# Sheet1.net
KiCad netlist of a schematic drawn in Altium Designer
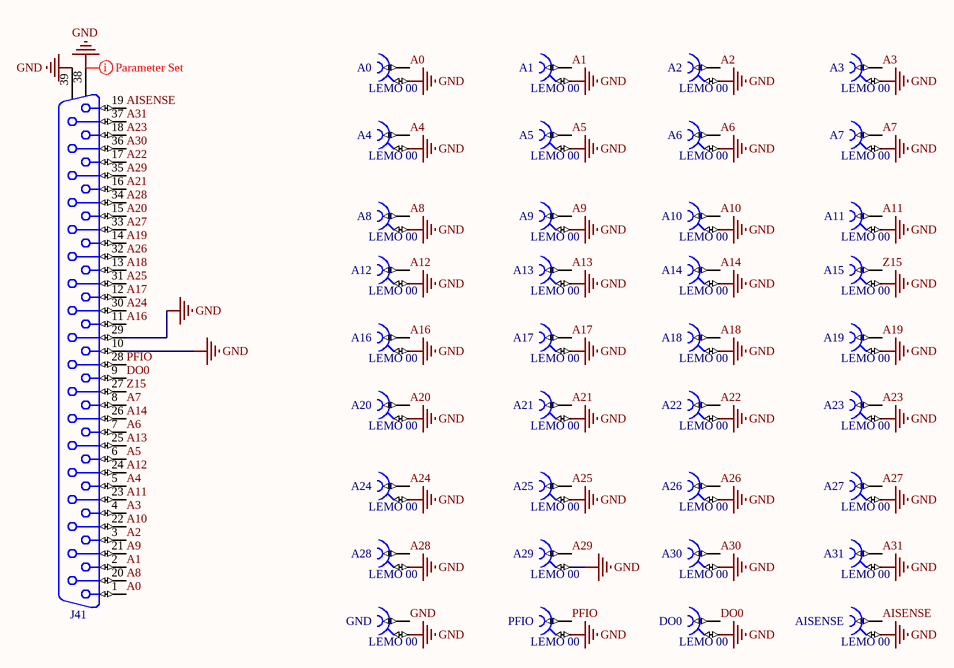
[diagram p0: Sheet1.SchDoc]

(export (version "E")
  (design (tool "Eeschema 10.0.6"))
  (components
    (comp (ref "A0")
      (value "LEMO 00")
      (footprint "LEMO_EPA.00.250.NTN")
      (fields
        (field (name "PART NUMBER") "LEMO_EPA.00.250.NTN")
        (field (name "MANUFACTURER") "LEMO")
        (field (name "MANUFACTURER PART NUMBER") "EPA.00.250.NTN")
        (field (name "AUTHOR") "CERN DEM JLC")
      )
      (libsource (lib "Connectors") (part "Coax_1Female_1Shield"))
    )
    (comp (ref "A1")
      (value "LEMO 00")
      (footprint "LEMO_EPA.00.250.NTN")
      (fields
        (field (name "PART NUMBER") "LEMO_EPA.00.250.NTN")
        (field (name "MANUFACTURER") "LEMO")
        (field (name "MANUFACTURER PART NUMBER") "EPA.00.250.NTN")
        (field (name "AUTHOR") "CERN DEM JLC")
      )
      (libsource (lib "Connectors") (part "Coax_1Female_1Shield"))
    )
    (comp (ref "A2")
      (value "LEMO 00")
      (footprint "LEMO_EPA.00.250.NTN")
      (fields
        (field (name "PART NUMBER") "LEMO_EPA.00.250.NTN")
        (field (name "MANUFACTURER") "LEMO")
        (field (name "MANUFACTURER PART NUMBER") "EPA.00.250.NTN")
        (field (name "AUTHOR") "CERN DEM JLC")
      )
      (libsource (lib "Connectors") (part "Coax_1Female_1Shield"))
    )
    (comp (ref "A3")
      (value "LEMO 00")
      (footprint "LEMO_EPA.00.250.NTN")
      (fields
        (field (name "PART NUMBER") "LEMO_EPA.00.250.NTN")
        (field (name "MANUFACTURER") "LEMO")
        (field (name "MANUFACTURER PART NUMBER") "EPA.00.250.NTN")
        (field (name "AUTHOR") "CERN DEM JLC")
      )
      (libsource (lib "Connectors") (part "Coax_1Female_1Shield"))
    )
    (comp (ref "A4")
      (value "LEMO 00")
      (footprint "LEMO_EPA.00.250.NTN")
      (fields
        (field (name "PART NUMBER") "LEMO_EPA.00.250.NTN")
        (field (name "MANUFACTURER") "LEMO")
        (field (name "MANUFACTURER PART NUMBER") "EPA.00.250.NTN")
        (field (name "AUTHOR") "CERN DEM JLC")
      )
      (libsource (lib "Connectors") (part "Coax_1Female_1Shield"))
    )
    (comp (ref "A5")
      (value "LEMO 00")
      (footprint "LEMO_EPA.00.250.NTN")
      (fields
        (field (name "PART NUMBER") "LEMO_EPA.00.250.NTN")
        (field (name "MANUFACTURER") "LEMO")
        (field (name "MANUFACTURER PART NUMBER") "EPA.00.250.NTN")
        (field (name "AUTHOR") "CERN DEM JLC")
      )
      (libsource (lib "Connectors") (part "Coax_1Female_1Shield"))
    )
    (comp (ref "A6")
      (value "LEMO 00")
      (footprint "LEMO_EPA.00.250.NTN")
      (fields
        (field (name "PART NUMBER") "LEMO_EPA.00.250.NTN")
        (field (name "MANUFACTURER") "LEMO")
        (field (name "MANUFACTURER PART NUMBER") "EPA.00.250.NTN")
        (field (name "AUTHOR") "CERN DEM JLC")
      )
      (libsource (lib "Connectors") (part "Coax_1Female_1Shield"))
    )
    (comp (ref "A7")
      (value "LEMO 00")
      (footprint "LEMO_EPA.00.250.NTN")
      (fields
        (field (name "PART NUMBER") "LEMO_EPA.00.250.NTN")
        (field (name "MANUFACTURER") "LEMO")
        (field (name "MANUFACTURER PART NUMBER") "EPA.00.250.NTN")
        (field (name "AUTHOR") "CERN DEM JLC")
      )
      (libsource (lib "Connectors") (part "Coax_1Female_1Shield"))
    )
    (comp (ref "A8")
      (value "LEMO 00")
      (footprint "LEMO_EPA.00.250.NTN")
      (fields
        (field (name "PART NUMBER") "LEMO_EPA.00.250.NTN")
        (field (name "MANUFACTURER") "LEMO")
        (field (name "MANUFACTURER PART NUMBER") "EPA.00.250.NTN")
        (field (name "AUTHOR") "CERN DEM JLC")
      )
      (libsource (lib "Connectors") (part "Coax_1Female_1Shield"))
    )
    (comp (ref "A9")
      (value "LEMO 00")
      (footprint "LEMO_EPA.00.250.NTN")
      (fields
        (field (name "PART NUMBER") "LEMO_EPA.00.250.NTN")
        (field (name "MANUFACTURER") "LEMO")
        (field (name "MANUFACTURER PART NUMBER") "EPA.00.250.NTN")
        (field (name "AUTHOR") "CERN DEM JLC")
      )
      (libsource (lib "Connectors") (part "Coax_1Female_1Shield"))
    )
    (comp (ref "A10")
      (value "LEMO 00")
      (footprint "LEMO_EPA.00.250.NTN")
      (fields
        (field (name "PART NUMBER") "LEMO_EPA.00.250.NTN")
        (field (name "MANUFACTURER") "LEMO")
        (field (name "MANUFACTURER PART NUMBER") "EPA.00.250.NTN")
        (field (name "AUTHOR") "CERN DEM JLC")
      )
      (libsource (lib "Connectors") (part "Coax_1Female_1Shield"))
    )
    (comp (ref "A11")
      (value "LEMO 00")
      (footprint "LEMO_EPA.00.250.NTN")
      (fields
        (field (name "PART NUMBER") "LEMO_EPA.00.250.NTN")
        (field (name "MANUFACTURER") "LEMO")
        (field (name "MANUFACTURER PART NUMBER") "EPA.00.250.NTN")
        (field (name "AUTHOR") "CERN DEM JLC")
      )
      (libsource (lib "Connectors") (part "Coax_1Female_1Shield"))
    )
    (comp (ref "A12")
      (value "LEMO 00")
      (footprint "LEMO_EPA.00.250.NTN")
      (fields
        (field (name "PART NUMBER") "LEMO_EPA.00.250.NTN")
        (field (name "MANUFACTURER") "LEMO")
        (field (name "MANUFACTURER PART NUMBER") "EPA.00.250.NTN")
        (field (name "AUTHOR") "CERN DEM JLC")
      )
      (libsource (lib "Connectors") (part "Coax_1Female_1Shield"))
    )
    (comp (ref "A13")
      (value "LEMO 00")
      (footprint "LEMO_EPA.00.250.NTN")
      (fields
        (field (name "PART NUMBER") "LEMO_EPA.00.250.NTN")
        (field (name "MANUFACTURER") "LEMO")
        (field (name "MANUFACTURER PART NUMBER") "EPA.00.250.NTN")
        (field (name "AUTHOR") "CERN DEM JLC")
      )
      (libsource (lib "Connectors") (part "Coax_1Female_1Shield"))
    )
    (comp (ref "A14")
      (value "LEMO 00")
      (footprint "LEMO_EPA.00.250.NTN")
      (fields
        (field (name "PART NUMBER") "LEMO_EPA.00.250.NTN")
        (field (name "MANUFACTURER") "LEMO")
        (field (name "MANUFACTURER PART NUMBER") "EPA.00.250.NTN")
        (field (name "AUTHOR") "CERN DEM JLC")
      )
      (libsource (lib "Connectors") (part "Coax_1Female_1Shield"))
    )
    (comp (ref "A15")
      (value "LEMO 00")
      (footprint "LEMO_EPA.00.250.NTN")
      (fields
        (field (name "PART NUMBER") "LEMO_EPA.00.250.NTN")
        (field (name "MANUFACTURER") "LEMO")
        (field (name "MANUFACTURER PART NUMBER") "EPA.00.250.NTN")
        (field (name "AUTHOR") "CERN DEM JLC")
      )
      (libsource (lib "Connectors") (part "Coax_1Female_1Shield"))
    )
    (comp (ref "A16")
      (value "LEMO 00")
      (footprint "LEMO_EPA.00.250.NTN")
      (fields
        (field (name "PART NUMBER") "LEMO_EPA.00.250.NTN")
        (field (name "MANUFACTURER") "LEMO")
        (field (name "MANUFACTURER PART NUMBER") "EPA.00.250.NTN")
        (field (name "AUTHOR") "CERN DEM JLC")
      )
      (libsource (lib "Connectors") (part "Coax_1Female_1Shield"))
    )
    (comp (ref "A17")
      (value "LEMO 00")
      (footprint "LEMO_EPA.00.250.NTN")
      (fields
        (field (name "PART NUMBER") "LEMO_EPA.00.250.NTN")
        (field (name "MANUFACTURER") "LEMO")
        (field (name "MANUFACTURER PART NUMBER") "EPA.00.250.NTN")
        (field (name "AUTHOR") "CERN DEM JLC")
      )
      (libsource (lib "Connectors") (part "Coax_1Female_1Shield"))
    )
    (comp (ref "A18")
      (value "LEMO 00")
      (footprint "LEMO_EPA.00.250.NTN")
      (fields
        (field (name "PART NUMBER") "LEMO_EPA.00.250.NTN")
        (field (name "MANUFACTURER") "LEMO")
        (field (name "MANUFACTURER PART NUMBER") "EPA.00.250.NTN")
        (field (name "AUTHOR") "CERN DEM JLC")
      )
      (libsource (lib "Connectors") (part "Coax_1Female_1Shield"))
    )
    (comp (ref "A19")
      (value "LEMO 00")
      (footprint "LEMO_EPA.00.250.NTN")
      (fields
        (field (name "PART NUMBER") "LEMO_EPA.00.250.NTN")
        (field (name "MANUFACTURER") "LEMO")
        (field (name "MANUFACTURER PART NUMBER") "EPA.00.250.NTN")
        (field (name "AUTHOR") "CERN DEM JLC")
      )
      (libsource (lib "Connectors") (part "Coax_1Female_1Shield"))
    )
    (comp (ref "A20")
      (value "LEMO 00")
      (footprint "LEMO_EPA.00.250.NTN")
      (fields
        (field (name "PART NUMBER") "LEMO_EPA.00.250.NTN")
        (field (name "MANUFACTURER") "LEMO")
        (field (name "MANUFACTURER PART NUMBER") "EPA.00.250.NTN")
        (field (name "AUTHOR") "CERN DEM JLC")
      )
      (libsource (lib "Connectors") (part "Coax_1Female_1Shield"))
    )
    (comp (ref "A21")
      (value "LEMO 00")
      (footprint "LEMO_EPA.00.250.NTN")
      (fields
        (field (name "PART NUMBER") "LEMO_EPA.00.250.NTN")
        (field (name "MANUFACTURER") "LEMO")
        (field (name "MANUFACTURER PART NUMBER") "EPA.00.250.NTN")
        (field (name "AUTHOR") "CERN DEM JLC")
      )
      (libsource (lib "Connectors") (part "Coax_1Female_1Shield"))
    )
    (comp (ref "A22")
      (value "LEMO 00")
      (footprint "LEMO_EPA.00.250.NTN")
      (fields
        (field (name "PART NUMBER") "LEMO_EPA.00.250.NTN")
        (field (name "MANUFACTURER") "LEMO")
        (field (name "MANUFACTURER PART NUMBER") "EPA.00.250.NTN")
        (field (name "AUTHOR") "CERN DEM JLC")
      )
      (libsource (lib "Connectors") (part "Coax_1Female_1Shield"))
    )
    (comp (ref "A23")
      (value "LEMO 00")
      (footprint "LEMO_EPA.00.250.NTN")
      (fields
        (field (name "PART NUMBER") "LEMO_EPA.00.250.NTN")
        (field (name "MANUFACTURER") "LEMO")
        (field (name "MANUFACTURER PART NUMBER") "EPA.00.250.NTN")
        (field (name "AUTHOR") "CERN DEM JLC")
      )
      (libsource (lib "Connectors") (part "Coax_1Female_1Shield"))
    )
    (comp (ref "A24")
      (value "LEMO 00")
      (footprint "LEMO_EPA.00.250.NTN")
      (fields
        (field (name "PART NUMBER") "LEMO_EPA.00.250.NTN")
        (field (name "MANUFACTURER") "LEMO")
        (field (name "MANUFACTURER PART NUMBER") "EPA.00.250.NTN")
        (field (name "AUTHOR") "CERN DEM JLC")
      )
      (libsource (lib "Connectors") (part "Coax_1Female_1Shield"))
    )
    (comp (ref "A25")
      (value "LEMO 00")
      (footprint "LEMO_EPA.00.250.NTN")
      (fields
        (field (name "PART NUMBER") "LEMO_EPA.00.250.NTN")
        (field (name "MANUFACTURER") "LEMO")
        (field (name "MANUFACTURER PART NUMBER") "EPA.00.250.NTN")
        (field (name "AUTHOR") "CERN DEM JLC")
      )
      (libsource (lib "Connectors") (part "Coax_1Female_1Shield"))
    )
    (comp (ref "A26")
      (value "LEMO 00")
      (footprint "LEMO_EPA.00.250.NTN")
      (fields
        (field (name "PART NUMBER") "LEMO_EPA.00.250.NTN")
        (field (name "MANUFACTURER") "LEMO")
        (field (name "MANUFACTURER PART NUMBER") "EPA.00.250.NTN")
        (field (name "AUTHOR") "CERN DEM JLC")
      )
      (libsource (lib "Connectors") (part "Coax_1Female_1Shield"))
    )
    (comp (ref "A27")
      (value "LEMO 00")
      (footprint "LEMO_EPA.00.250.NTN")
      (fields
        (field (name "PART NUMBER") "LEMO_EPA.00.250.NTN")
        (field (name "MANUFACTURER") "LEMO")
        (field (name "MANUFACTURER PART NUMBER") "EPA.00.250.NTN")
        (field (name "AUTHOR") "CERN DEM JLC")
      )
      (libsource (lib "Connectors") (part "Coax_1Female_1Shield"))
    )
    (comp (ref "A28")
      (value "LEMO 00")
      (footprint "LEMO_EPA.00.250.NTN")
      (fields
        (field (name "PART NUMBER") "LEMO_EPA.00.250.NTN")
        (field (name "MANUFACTURER") "LEMO")
        (field (name "MANUFACTURER PART NUMBER") "EPA.00.250.NTN")
        (field (name "AUTHOR") "CERN DEM JLC")
      )
      (libsource (lib "Connectors") (part "Coax_1Female_1Shield"))
    )
    (comp (ref "A29")
      (value "LEMO 00")
      (footprint "LEMO_EPA.00.250.NTN")
      (fields
        (field (name "PART NUMBER") "LEMO_EPA.00.250.NTN")
        (field (name "MANUFACTURER") "LEMO")
        (field (name "MANUFACTURER PART NUMBER") "EPA.00.250.NTN")
        (field (name "AUTHOR") "CERN DEM JLC")
      )
      (libsource (lib "Connectors") (part "Coax_1Female_1Shield"))
    )
    (comp (ref "A30")
      (value "LEMO 00")
      (footprint "LEMO_EPA.00.250.NTN")
      (fields
        (field (name "PART NUMBER") "LEMO_EPA.00.250.NTN")
        (field (name "MANUFACTURER") "LEMO")
        (field (name "MANUFACTURER PART NUMBER") "EPA.00.250.NTN")
        (field (name "AUTHOR") "CERN DEM JLC")
      )
      (libsource (lib "Connectors") (part "Coax_1Female_1Shield"))
    )
    (comp (ref "A31")
      (value "LEMO 00")
      (footprint "LEMO_EPA.00.250.NTN")
      (fields
        (field (name "PART NUMBER") "LEMO_EPA.00.250.NTN")
        (field (name "MANUFACTURER") "LEMO")
        (field (name "MANUFACTURER PART NUMBER") "EPA.00.250.NTN")
        (field (name "AUTHOR") "CERN DEM JLC")
      )
      (libsource (lib "Connectors") (part "Coax_1Female_1Shield"))
    )
    (comp (ref "AISENSE")
      (value "LEMO 00")
      (footprint "LEMO_EPA.00.250.NTN")
      (fields
        (field (name "PART NUMBER") "LEMO_EPA.00.250.NTN")
        (field (name "MANUFACTURER") "LEMO")
        (field (name "MANUFACTURER PART NUMBER") "EPA.00.250.NTN")
        (field (name "AUTHOR") "CERN DEM JLC")
      )
      (libsource (lib "Connectors") (part "Coax_1Female_1Shield"))
    )
    (comp (ref "DO0")
      (value "LEMO 00")
      (footprint "LEMO_EPA.00.250.NTN")
      (fields
        (field (name "PART NUMBER") "LEMO_EPA.00.250.NTN")
        (field (name "MANUFACTURER") "LEMO")
        (field (name "MANUFACTURER PART NUMBER") "EPA.00.250.NTN")
        (field (name "AUTHOR") "CERN DEM JLC")
      )
      (libsource (lib "Connectors") (part "Coax_1Female_1Shield"))
    )
    (comp (ref "GND")
      (value "LEMO 00")
      (footprint "LEMO_EPA.00.250.NTN")
      (fields
        (field (name "PART NUMBER") "LEMO_EPA.00.250.NTN")
        (field (name "MANUFACTURER") "LEMO")
        (field (name "MANUFACTURER PART NUMBER") "EPA.00.250.NTN")
        (field (name "AUTHOR") "CERN DEM JLC")
      )
      (libsource (lib "Connectors") (part "Coax_1Female_1Shield"))
    )
    (comp (ref "J41")
      (value "D-SUB37F")
      (footprint "NORCOMP_172-037-242R011")
      (description "Connector D-sub 37 Female")
      (fields
        (field (name "PART NUMBER") "NORCOMP_172-037-242R011")
        (field (name "MANUFACTURER") "NORCOMP")
        (field (name "AUTHOR") "CERN DEM MR")
      )
      (libsource (lib "Connectors") (part "Connector D-sub 37 Female"))
    )
    (comp (ref "PFIO")
      (value "LEMO 00")
      (footprint "LEMO_EPA.00.250.NTN")
      (fields
        (field (name "PART NUMBER") "LEMO_EPA.00.250.NTN")
        (field (name "MANUFACTURER") "LEMO")
        (field (name "MANUFACTURER PART NUMBER") "EPA.00.250.NTN")
        (field (name "AUTHOR") "CERN DEM JLC")
      )
      (libsource (lib "Connectors") (part "Coax_1Female_1Shield"))
    )
  )
  (nets
    (net (code "1") (name "/A0") (class "Default")
      (node (ref "A0") (pin "1") (pinfunction "1_1") (pintype "bidirectional"))
      (node (ref "J41") (pin "1") (pinfunction "1_1") (pintype "bidirectional"))
    )
    (net (code "2") (name "/A1") (class "Default")
      (node (ref "A1") (pin "1") (pinfunction "1_1") (pintype "bidirectional"))
      (node (ref "J41") (pin "2") (pinfunction "2_2") (pintype "bidirectional"))
    )
    (net (code "3") (name "/A2") (class "Default")
      (node (ref "A2") (pin "1") (pinfunction "1_1") (pintype "bidirectional"))
      (node (ref "J41") (pin "3") (pinfunction "3_3") (pintype "bidirectional"))
    )
    (net (code "4") (name "/A3") (class "Default")
      (node (ref "A3") (pin "1") (pinfunction "1_1") (pintype "bidirectional"))
      (node (ref "J41") (pin "4") (pinfunction "4_4") (pintype "bidirectional"))
    )
    (net (code "5") (name "/A4") (class "Default")
      (node (ref "A4") (pin "1") (pinfunction "1_1") (pintype "bidirectional"))
      (node (ref "J41") (pin "5") (pinfunction "5_5") (pintype "bidirectional"))
    )
    (net (code "6") (name "/A5") (class "Default")
      (node (ref "A5") (pin "1") (pinfunction "1_1") (pintype "bidirectional"))
      (node (ref "J41") (pin "6") (pinfunction "6_6") (pintype "bidirectional"))
    )
    (net (code "7") (name "/A6") (class "Default")
      (node (ref "A6") (pin "1") (pinfunction "1_1") (pintype "bidirectional"))
      (node (ref "J41") (pin "7") (pinfunction "7_7") (pintype "bidirectional"))
    )
    (net (code "8") (name "/A7") (class "Default")
      (node (ref "A7") (pin "1") (pinfunction "1_1") (pintype "bidirectional"))
      (node (ref "J41") (pin "8") (pinfunction "8_8") (pintype "bidirectional"))
    )
    (net (code "9") (name "/A8") (class "Default")
      (node (ref "A8") (pin "1") (pinfunction "1_1") (pintype "bidirectional"))
      (node (ref "J41") (pin "20") (pinfunction "20_20") (pintype "bidirectional"))
    )
    (net (code "10") (name "/A9") (class "Default")
      (node (ref "A9") (pin "1") (pinfunction "1_1") (pintype "bidirectional"))
      (node (ref "J41") (pin "21") (pinfunction "21_21") (pintype "bidirectional"))
    )
    (net (code "11") (name "/A10") (class "Default")
      (node (ref "A10") (pin "1") (pinfunction "1_1") (pintype "bidirectional"))
      (node (ref "J41") (pin "22") (pinfunction "22_22") (pintype "bidirectional"))
    )
    (net (code "12") (name "/A11") (class "Default")
      (node (ref "A11") (pin "1") (pinfunction "1_1") (pintype "bidirectional"))
      (node (ref "J41") (pin "23") (pinfunction "23_23") (pintype "bidirectional"))
    )
    (net (code "13") (name "/A12") (class "Default")
      (node (ref "A12") (pin "1") (pinfunction "1_1") (pintype "bidirectional"))
      (node (ref "J41") (pin "24") (pinfunction "24_24") (pintype "bidirectional"))
    )
    (net (code "14") (name "/A13") (class "Default")
      (node (ref "A13") (pin "1") (pinfunction "1_1") (pintype "bidirectional"))
      (node (ref "J41") (pin "25") (pinfunction "25_25") (pintype "bidirectional"))
    )
    (net (code "15") (name "/A14") (class "Default")
      (node (ref "A14") (pin "1") (pinfunction "1_1") (pintype "bidirectional"))
      (node (ref "J41") (pin "26") (pinfunction "26_26") (pintype "bidirectional"))
    )
    (net (code "16") (name "/A16") (class "Default")
      (node (ref "A16") (pin "1") (pinfunction "1_1") (pintype "bidirectional"))
      (node (ref "J41") (pin "11") (pinfunction "11_11") (pintype "bidirectional"))
    )
    (net (code "17") (name "/A17") (class "Default")
      (node (ref "A17") (pin "1") (pinfunction "1_1") (pintype "bidirectional"))
      (node (ref "J41") (pin "12") (pinfunction "12_12") (pintype "bidirectional"))
    )
    (net (code "18") (name "/A18") (class "Default")
      (node (ref "A18") (pin "1") (pinfunction "1_1") (pintype "bidirectional"))
      (node (ref "J41") (pin "13") (pinfunction "13_13") (pintype "bidirectional"))
    )
    (net (code "19") (name "/A19") (class "Default")
      (node (ref "A19") (pin "1") (pinfunction "1_1") (pintype "bidirectional"))
      (node (ref "J41") (pin "14") (pinfunction "14_14") (pintype "bidirectional"))
    )
    (net (code "20") (name "/A20") (class "Default")
      (node (ref "A20") (pin "1") (pinfunction "1_1") (pintype "bidirectional"))
      (node (ref "J41") (pin "15") (pinfunction "15_15") (pintype "bidirectional"))
    )
    (net (code "21") (name "/A21") (class "Default")
      (node (ref "A21") (pin "1") (pinfunction "1_1") (pintype "bidirectional"))
      (node (ref "J41") (pin "16") (pinfunction "16_16") (pintype "bidirectional"))
    )
    (net (code "22") (name "/A22") (class "Default")
      (node (ref "A22") (pin "1") (pinfunction "1_1") (pintype "bidirectional"))
      (node (ref "J41") (pin "17") (pinfunction "17_17") (pintype "bidirectional"))
    )
    (net (code "23") (name "/A23") (class "Default")
      (node (ref "A23") (pin "1") (pinfunction "1_1") (pintype "bidirectional"))
      (node (ref "J41") (pin "18") (pinfunction "18_18") (pintype "bidirectional"))
    )
    (net (code "24") (name "/A24") (class "Default")
      (node (ref "A24") (pin "1") (pinfunction "1_1") (pintype "bidirectional"))
      (node (ref "J41") (pin "30") (pinfunction "30_30") (pintype "bidirectional"))
    )
    (net (code "25") (name "/A25") (class "Default")
      (node (ref "A25") (pin "1") (pinfunction "1_1") (pintype "bidirectional"))
      (node (ref "J41") (pin "31") (pinfunction "31_31") (pintype "bidirectional"))
    )
    (net (code "26") (name "/A26") (class "Default")
      (node (ref "A26") (pin "1") (pinfunction "1_1") (pintype "bidirectional"))
      (node (ref "J41") (pin "32") (pinfunction "32_32") (pintype "bidirectional"))
    )
    (net (code "27") (name "/A27") (class "Default")
      (node (ref "A27") (pin "1") (pinfunction "1_1") (pintype "bidirectional"))
      (node (ref "J41") (pin "33") (pinfunction "33_33") (pintype "bidirectional"))
    )
    (net (code "28") (name "/A28") (class "Default")
      (node (ref "A28") (pin "1") (pinfunction "1_1") (pintype "bidirectional"))
      (node (ref "J41") (pin "34") (pinfunction "34_34") (pintype "bidirectional"))
    )
    (net (code "29") (name "/A29") (class "Default")
      (node (ref "A29") (pin "1") (pinfunction "1_1") (pintype "bidirectional"))
      (node (ref "J41") (pin "35") (pinfunction "35_35") (pintype "bidirectional"))
    )
    (net (code "30") (name "/A30") (class "Default")
      (node (ref "A30") (pin "1") (pinfunction "1_1") (pintype "bidirectional"))
      (node (ref "J41") (pin "36") (pinfunction "36_36") (pintype "bidirectional"))
    )
    (net (code "31") (name "/A31") (class "Default")
      (node (ref "A31") (pin "1") (pinfunction "1_1") (pintype "bidirectional"))
      (node (ref "J41") (pin "37") (pinfunction "37_37") (pintype "bidirectional"))
    )
    (net (code "32") (name "/AISENSE") (class "Default")
      (node (ref "AISENSE") (pin "1") (pinfunction "1_1") (pintype "bidirectional"))
      (node (ref "J41") (pin "19") (pinfunction "19_19") (pintype "bidirectional"))
    )
    (net (code "33") (name "/DO0") (class "Default")
      (node (ref "DO0") (pin "1") (pinfunction "1_1") (pintype "bidirectional"))
      (node (ref "J41") (pin "9") (pinfunction "9_9") (pintype "bidirectional"))
    )
    (net (code "34") (name "/PFIO") (class "Default")
      (node (ref "J41") (pin "28") (pinfunction "28_28") (pintype "bidirectional"))
      (node (ref "PFIO") (pin "1") (pinfunction "1_1") (pintype "bidirectional"))
    )
    (net (code "35") (name "/Z15") (class "Default")
      (node (ref "A15") (pin "1") (pinfunction "1_1") (pintype "bidirectional"))
      (node (ref "J41") (pin "27") (pinfunction "27_27") (pintype "bidirectional"))
    )
    (net (code "36") (name "GND") (class "Default")
      (node (ref "A0") (pin "2") (pinfunction "2_2") (pintype "bidirectional"))
      (node (ref "A1") (pin "2") (pinfunction "2_2") (pintype "bidirectional"))
      (node (ref "A10") (pin "2") (pinfunction "2_2") (pintype "bidirectional"))
      (node (ref "A11") (pin "2") (pinfunction "2_2") (pintype "bidirectional"))
      (node (ref "A12") (pin "2") (pinfunction "2_2") (pintype "bidirectional"))
      (node (ref "A13") (pin "2") (pinfunction "2_2") (pintype "bidirectional"))
      (node (ref "A14") (pin "2") (pinfunction "2_2") (pintype "bidirectional"))
      (node (ref "A15") (pin "2") (pinfunction "2_2") (pintype "bidirectional"))
      (node (ref "A16") (pin "2") (pinfunction "2_2") (pintype "bidirectional"))
      (node (ref "A17") (pin "2") (pinfunction "2_2") (pintype "bidirectional"))
      (node (ref "A18") (pin "2") (pinfunction "2_2") (pintype "bidirectional"))
      (node (ref "A19") (pin "2") (pinfunction "2_2") (pintype "bidirectional"))
      (node (ref "A2") (pin "2") (pinfunction "2_2") (pintype "bidirectional"))
      (node (ref "A20") (pin "2") (pinfunction "2_2") (pintype "bidirectional"))
      (node (ref "A21") (pin "2") (pinfunction "2_2") (pintype "bidirectional"))
      (node (ref "A22") (pin "2") (pinfunction "2_2") (pintype "bidirectional"))
      (node (ref "A23") (pin "2") (pinfunction "2_2") (pintype "bidirectional"))
      (node (ref "A24") (pin "2") (pinfunction "2_2") (pintype "bidirectional"))
      (node (ref "A25") (pin "2") (pinfunction "2_2") (pintype "bidirectional"))
      (node (ref "A26") (pin "2") (pinfunction "2_2") (pintype "bidirectional"))
      (node (ref "A27") (pin "2") (pinfunction "2_2") (pintype "bidirectional"))
      (node (ref "A28") (pin "2") (pinfunction "2_2") (pintype "bidirectional"))
      (node (ref "A29") (pin "2") (pinfunction "2_2") (pintype "bidirectional"))
      (node (ref "A3") (pin "2") (pinfunction "2_2") (pintype "bidirectional"))
      (node (ref "A30") (pin "2") (pinfunction "2_2") (pintype "bidirectional"))
      (node (ref "A31") (pin "2") (pinfunction "2_2") (pintype "bidirectional"))
      (node (ref "A4") (pin "2") (pinfunction "2_2") (pintype "bidirectional"))
      (node (ref "A5") (pin "2") (pinfunction "2_2") (pintype "bidirectional"))
      (node (ref "A6") (pin "2") (pinfunction "2_2") (pintype "bidirectional"))
      (node (ref "A7") (pin "2") (pinfunction "2_2") (pintype "bidirectional"))
      (node (ref "A8") (pin "2") (pinfunction "2_2") (pintype "bidirectional"))
      (node (ref "A9") (pin "2") (pinfunction "2_2") (pintype "bidirectional"))
      (node (ref "AISENSE") (pin "2") (pinfunction "2_2") (pintype "bidirectional"))
      (node (ref "DO0") (pin "2") (pinfunction "2_2") (pintype "bidirectional"))
      (node (ref "GND") (pin "1") (pinfunction "1_1") (pintype "bidirectional"))
      (node (ref "GND") (pin "2") (pinfunction "2_2") (pintype "bidirectional"))
      (node (ref "J41") (pin "10") (pinfunction "10_10") (pintype "bidirectional"))
      (node (ref "J41") (pin "29") (pinfunction "29_29") (pintype "bidirectional"))
      (node (ref "J41") (pin "38") (pinfunction "38_38") (pintype "passive"))
      (node (ref "J41") (pin "39") (pinfunction "39_39") (pintype "passive"))
      (node (ref "PFIO") (pin "2") (pinfunction "2_2") (pintype "bidirectional"))
    )
  )
)
